# 5kHZ_LO_LPF.net
KiCad netlist of a schematic drawn in Altium Designer
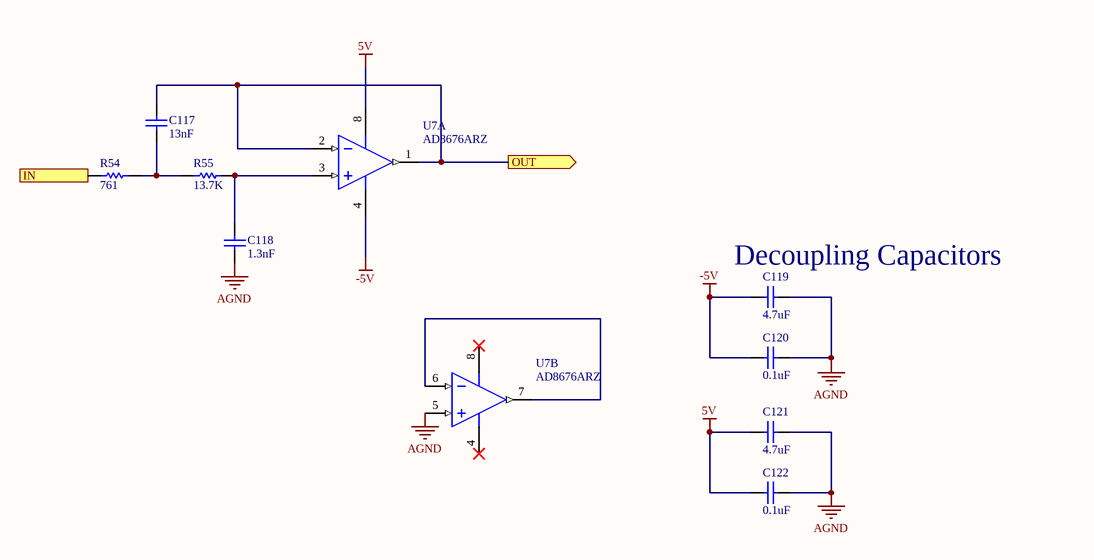
[diagram p0: 5kHZ_LO_LPF.SchDoc]

(export (version "E")
  (design (tool "Eeschema 10.0.6"))
  (components
    (comp (ref "C117")
      (value "13nF")
      (footprint "0402_Cap")
      (description "Capacitor, 16nF, 0805, 25V")
      (libsource (lib "Arturo_Approved") (part "08051C163JAT2A"))
    )
    (comp (ref "C118")
      (value "1.3nF")
      (footprint "0402_Cap")
      (description "Capacitor, 1.6nF, 0805, 25V")
      (libsource (lib "Arturo_Approved") (part "GRM2165C2A162JA01D"))
    )
    (comp (ref "C119")
      (value "4.7uF")
      (footprint "0402_Cap")
      (description "Capacitor, 4.7uF, 0805")
      (libsource (lib "Arturo_Approved") (part "CL21A475KAQNNNE"))
    )
    (comp (ref "C120")
      (value "0.1uF")
      (footprint "0402_Cap")
      (description "Capacitor, 0.1uF, 0805")
      (libsource (lib "Arturo_Approved") (part "CL21B104KACNNNC"))
    )
    (comp (ref "C121")
      (value "4.7uF")
      (footprint "0402_Cap")
      (description "Capacitor, 4.7uF, 0805")
      (libsource (lib "Arturo_Approved") (part "CL21A475KAQNNNE"))
    )
    (comp (ref "C122")
      (value "0.1uF")
      (footprint "0402_Cap")
      (description "Capacitor, 0.1uF, 0805")
      (libsource (lib "Arturo_Approved") (part "CL21B104KACNNNC"))
    )
    (comp (ref "R54")
      (value "761")
      (footprint "0402_Res")
      (description "1.65k")
      (libsource (lib "Arturo_Approved") (part "RC0805FR-071K65L"))
    )
    (comp (ref "R55")
      (value "13.7K")
      (footprint "0402_Res")
      (description "5.9k")
      (libsource (lib "Arturo_Approved") (part "RC0805FR-075K9L"))
    )
    (comp (ref "U7")
      (value "AD8676ARZ")
      (footprint "ADI-R-8_M")
      (fields (field (name "GENERIC PART NUMBER") "AD8676") (field (name "MANUFACTURER") "Analog Devices"))
      (libsource (lib "Altium Content Vault") (part "ADI-OP29X-R-8"))
    )
  )
  (nets
    (net (code "1") (name "-5V") (class "Default")
      (node (ref "C119") (pin "1") (pinfunction "1_1") (pintype "passive"))
      (node (ref "C120") (pin "1") (pinfunction "1_1") (pintype "passive"))
      (node (ref "U7") (pin "4") (pinfunction "-V_4") (pintype "power_in"))
    )
    (net (code "2") (name "/IN") (class "Default")
      (node (ref "R54") (pin "1") (pinfunction "1_1") (pintype "passive"))
    )
    (net (code "3") (name "/OUT") (class "Default")
      (node (ref "C117") (pin "2") (pinfunction "2_2") (pintype "passive"))
      (node (ref "U7") (pin "1") (pinfunction "OUT_A_1") (pintype "output"))
      (node (ref "U7") (pin "2") (pinfunction "-IN_A_2") (pintype "input"))
    )
    (net (code "4") (name "5V") (class "Default")
      (node (ref "C121") (pin "1") (pinfunction "1_1") (pintype "passive"))
      (node (ref "C122") (pin "1") (pinfunction "1_1") (pintype "passive"))
      (node (ref "U7") (pin "8") (pinfunction "+V_8") (pintype "power_in"))
    )
    (net (code "5") (name "AGND") (class "Default")
      (node (ref "C118") (pin "1") (pinfunction "1_1") (pintype "passive"))
      (node (ref "C119") (pin "2") (pinfunction "2_2") (pintype "passive"))
      (node (ref "C120") (pin "2") (pinfunction "2_2") (pintype "passive"))
      (node (ref "C121") (pin "2") (pinfunction "2_2") (pintype "passive"))
      (node (ref "C122") (pin "2") (pinfunction "2_2") (pintype "passive"))
      (node (ref "U7") (pin "5") (pinfunction "+IN_B_5") (pintype "input"))
    )
    (net (code "6") (name "Net-(C117-Pad1)") (class "Default")
      (node (ref "C117") (pin "1") (pinfunction "1_1") (pintype "passive"))
      (node (ref "R54") (pin "2") (pinfunction "2_2") (pintype "passive"))
      (node (ref "R55") (pin "1") (pinfunction "1_1") (pintype "passive"))
    )
    (net (code "7") (name "Net-(U7A-+IN_A)") (class "Default")
      (node (ref "C118") (pin "2") (pinfunction "2_2") (pintype "passive"))
      (node (ref "R55") (pin "2") (pinfunction "2_2") (pintype "passive"))
      (node (ref "U7") (pin "3") (pinfunction "+IN_A_3") (pintype "input"))
    )
    (net (code "8") (name "Net-(U7B--IN_B)") (class "Default")
      (node (ref "U7") (pin "6") (pinfunction "-IN_B_6") (pintype "input"))
      (node (ref "U7") (pin "7") (pinfunction "OUT_B_7") (pintype "output"))
    )
    (net (code "9") (name "unconnected-(U7B-+V-Pad8)") (class "Default")
      (node (ref "U7") (pin "8") (pinfunction "+V_8") (pintype "power_in+no_connect"))
    )
    (net (code "10") (name "unconnected-(U7B--V-Pad4)") (class "Default")
      (node (ref "U7") (pin "4") (pinfunction "-V_4") (pintype "power_in+no_connect"))
    )
  )
)
